# 3_waffling80-MXHS_mcu.net
KiCad netlist of a schematic drawn in Altium Designer
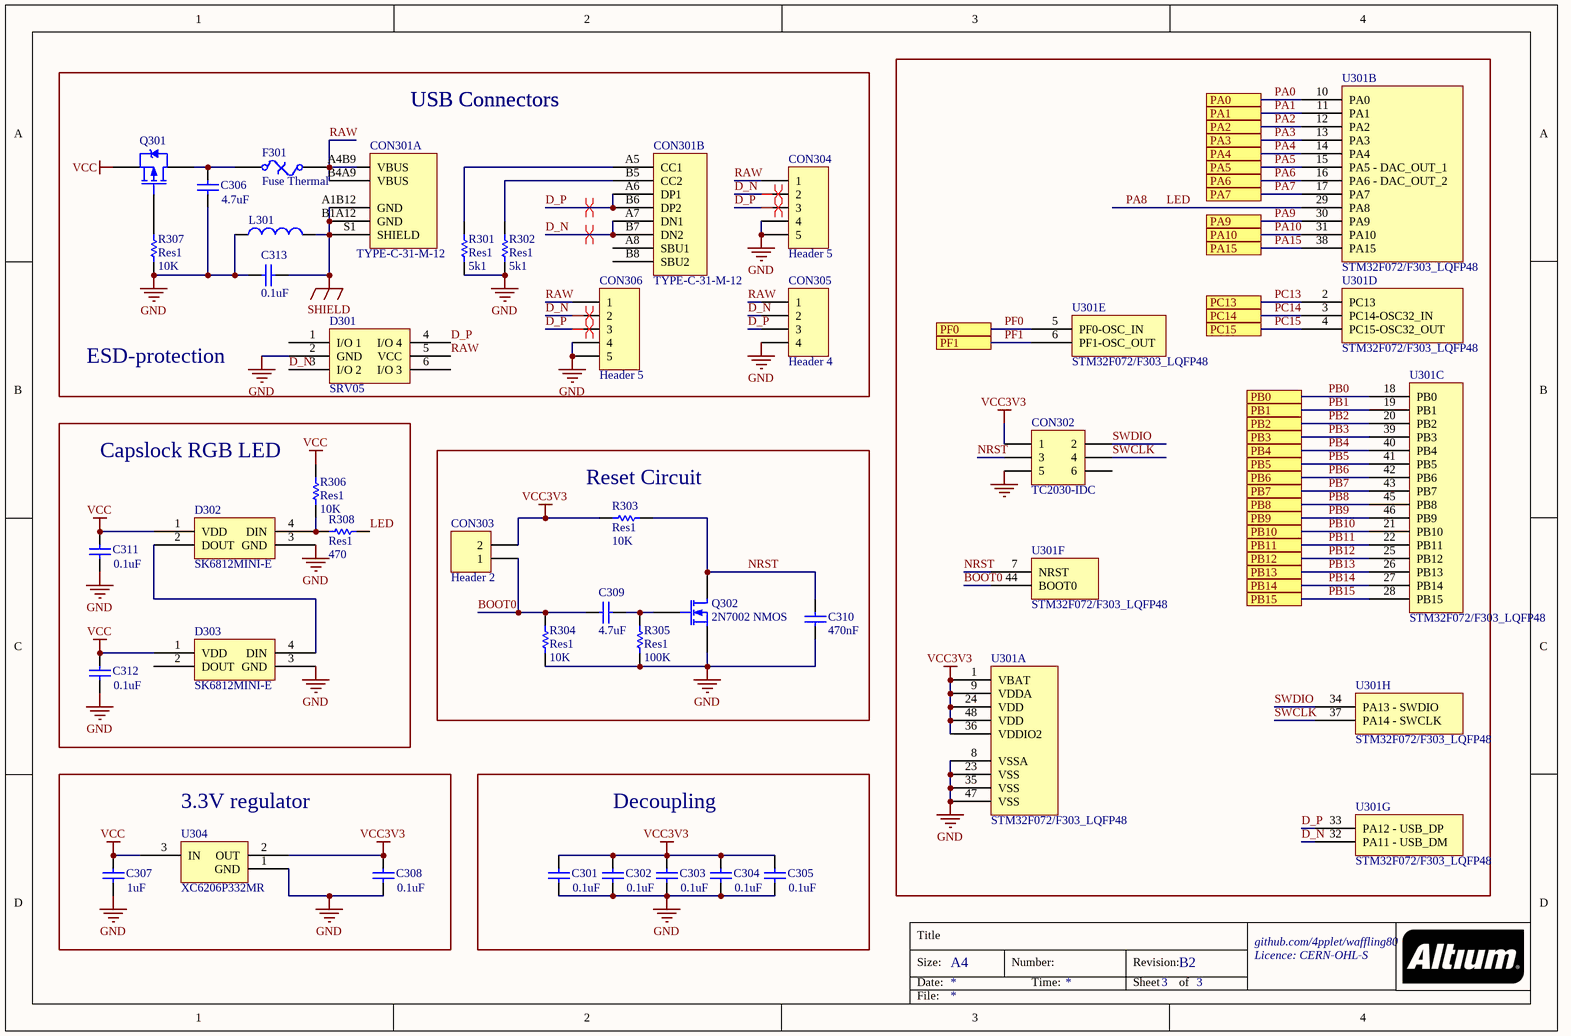
[diagram p0: 3_waffling80-MXHS_mcu.SchDoc]

(export (version "E")
  (design (tool "Eeschema 10.0.6"))
  (components
    (comp (ref "C301")
      (value "0.1uF")
      (footprint "C0603[1608]")
      (description "Capacitor")
      (fields (field (name "LCSC PART #") "C14663") (field (name "MRF.PART") "CC0603KRX7R9BB104"))
      (libsource (lib "Miscellaneous Devices") (part "Cap"))
    )
    (comp (ref "C302")
      (value "0.1uF")
      (footprint "C0603[1608]")
      (description "Capacitor")
      (fields (field (name "LCSC PART #") "C14663") (field (name "MRF.PART") "CC0603KRX7R9BB104"))
      (libsource (lib "Miscellaneous Devices") (part "Cap"))
    )
    (comp (ref "C303")
      (value "0.1uF")
      (footprint "C0603[1608]")
      (description "Capacitor")
      (fields (field (name "LCSC PART #") "C14663") (field (name "MRF.PART") "CC0603KRX7R9BB104"))
      (libsource (lib "Miscellaneous Devices") (part "Cap"))
    )
    (comp (ref "C304")
      (value "0.1uF")
      (footprint "C0603[1608]")
      (description "Capacitor")
      (fields (field (name "LCSC PART #") "C14663") (field (name "MRF.PART") "CC0603KRX7R9BB104"))
      (libsource (lib "Miscellaneous Devices") (part "Cap"))
    )
    (comp (ref "C305")
      (value "0.1uF")
      (footprint "C0603[1608]")
      (description "Capacitor")
      (fields (field (name "LCSC PART #") "C14663") (field (name "MRF.PART") "CC0603KRX7R9BB104"))
      (libsource (lib "Miscellaneous Devices") (part "Cap"))
    )
    (comp (ref "C306")
      (value "4.7uF")
      (footprint "C0603[1608]")
      (description "Capacitor")
      (fields (field (name "LCSC PART #") "C19666") (field (name "MRF.PART") "CL10A475KO8NNNC"))
      (libsource (lib "Miscellaneous Devices") (part "Cap"))
    )
    (comp (ref "C307")
      (value "1uF")
      (footprint "C0603[1608]")
      (description "Capacitor")
      (fields (field (name "LCSC PART #") "C15849") (field (name "MRF.PART") "CL10A105KB8NNNC"))
      (libsource (lib "Miscellaneous Devices") (part "Cap"))
    )
    (comp (ref "C308")
      (value "0.1uF")
      (footprint "C0603[1608]")
      (description "Capacitor")
      (fields (field (name "LCSC PART #") "C14663") (field (name "MRF.PART") "CC0603KRX7R9BB104"))
      (libsource (lib "Miscellaneous Devices") (part "Cap"))
    )
    (comp (ref "C309")
      (value "4.7uF")
      (footprint "C0603[1608]")
      (description "Capacitor")
      (fields (field (name "LCSC PART #") "C19666") (field (name "MRF.PART") "CL10A475KO8NNNC"))
      (libsource (lib "Miscellaneous Devices") (part "Cap"))
    )
    (comp (ref "C310")
      (value "470nF")
      (footprint "C0603[1608]")
      (description "Capacitor")
      (fields (field (name "LCSC PART #") "C1623") (field (name "MRF.PART") "CL10B474KA8NNNC"))
      (libsource (lib "Miscellaneous Devices") (part "Cap"))
    )
    (comp (ref "C311")
      (value "0.1uF")
      (footprint "C0603[1608]")
      (description "Capacitor")
      (fields (field (name "LCSC PART #") "C14663") (field (name "MRF.PART") "CC0603KRX7R9BB104"))
      (libsource (lib "Miscellaneous Devices") (part "Cap"))
    )
    (comp (ref "C312")
      (value "0.1uF")
      (footprint "C0603[1608]")
      (description "Capacitor")
      (fields (field (name "LCSC PART #") "C14663") (field (name "MRF.PART") "CC0603KRX7R9BB104"))
      (libsource (lib "Miscellaneous Devices") (part "Cap"))
    )
    (comp (ref "C313")
      (value "0.1uF")
      (footprint "C0603[1608]")
      (description "Capacitor")
      (fields (field (name "LCSC PART #") "C14663") (field (name "MRF.PART") "CC0603KRX7R9BB104"))
      (libsource (lib "Miscellaneous Devices") (part "Cap"))
    )
    (comp (ref "CON301")
      (value "TYPE-C-31-M-12")
      (footprint "TYPE-C-31-M-12")
      (fields (field (name "LCSC PART #") "C165948"))
      (libsource (lib "Schlib1") (part "TYPE-C-31-M-12"))
    )
    (comp (ref "CON302")
      (value "TC2030-IDC")
      (footprint "TC2030-IDC-NL")
      (description "Header, 3-Pin, Dual row")
      (libsource (lib "Miscellaneous Connectors") (part "Header 3X2"))
    )
    (comp (ref "CON303")
      (value "Header 2")
      (footprint "HDR1X2")
      (description "Header, 2-Pin")
      (libsource (lib "Miscellaneous Connectors") (part "Header 2"))
    )
    (comp (ref "CON304")
      (value "Header 5")
      (footprint "UDB_combo_JST_MOLEX")
      (description "JST for USB daughter board")
      (fields (field (name "LCSC PART #") "C160404") (field (name "MRF.PART") "SM04B-SRSS-TB(LF)(SN)"))
      (libsource (lib "Miscellaneous Connectors") (part "Header 5"))
    )
    (comp (ref "CON305")
      (value "Header 4")
      (footprint "HDR1X4")
      (description "Header, 4-Pin")
      (libsource (lib "Miscellaneous Connectors") (part "Header 4"))
    )
    (comp (ref "CON306")
      (value "Header 5")
      (footprint "Molex 781710004")
      (description "JST for USB daughter board")
      (fields (field (name "LCSC PART #") "C588524") (field (name "MRF.PART") "781710004"))
      (libsource (lib "Miscellaneous Connectors") (part "Header 5"))
    )
    (comp (ref "D301")
      (value "SRV05")
      (footprint "SOT-23-6")
      (fields (field (name "LCSC PART #") "C85364") (field (name "MRF.PART") "SRV05-4-P-T7"))
      (libsource (lib "Keebs") (part "SRV05"))
    )
    (comp (ref "D302")
      (value "SK6812MINI-E")
      (footprint "SK6812MINI-E - shaped")
      (fields (field (name "LCSC PART #") "C524051") (field (name "MRF.PART") "DY-S352818/RGBC/6812-2T"))
      (libsource (lib "Keebs") (part "SK6812MINI-E"))
    )
    (comp (ref "D303")
      (value "SK6812MINI-E")
      (footprint "SK6812MINI-E - shaped")
      (fields (field (name "LCSC PART #") "C524051") (field (name "MRF.PART") "DY-S352818/RGBC/6812-2T"))
      (libsource (lib "Keebs") (part "SK6812MINI-E"))
    )
    (comp (ref "F301")
      (value "Fuse Thermal")
      (footprint "C1206[3216]")
      (description "Thermal Fuse")
      (fields (field (name "LCSC PART #") "C135338") (field (name "MRF.PART") "ASMD1206-050"))
      (libsource (lib "Miscellaneous Devices") (part "Fuse Thermal"))
    )
    (comp (ref "L301")
      (value "Inductor")
      (footprint "L0805")
      (fields (field (name "LCSC PART #") "C1015") (field (name "MRF.PART") "GZ2012D101TF"))
      (libsource (lib "Simulation Generic Components") (part "Inductor"))
    )
    (comp (ref "Q301")
      (value "PMOS-2")
      (footprint "SOT-23-3")
      (description "P-Channel Power MOSFET")
      (fields (field (name "LCSC PART #") "C10487") (field (name "MRF.PART") "SI2301CDS-T1-GE3"))
      (libsource (lib "Miscellaneous Devices") (part "PMOS-2"))
    )
    (comp (ref "Q302")
      (value "2N7002 NMOS")
      (footprint "SOT-23-3")
      (description "N-Channel MOSFET")
      (fields (field (name "LCSC PART #") "C8545") (field (name "MRF.PART") "2N7002"))
      (libsource (lib "Miscellaneous Devices") (part "MOSFET-N"))
    )
    (comp (ref "R301")
      (value "Res1")
      (footprint "R0603[1608]")
      (description "Resistor")
      (fields
        (field (name "ALTIUM_VALUE") "5k1")
        (field (name "LCSC PART #") "C23186")
        (field (name "MRF.PART") "0603WAF5101T5E")
      )
      (libsource (lib "Miscellaneous Devices") (part "Res1"))
    )
    (comp (ref "R302")
      (value "Res1")
      (footprint "R0603[1608]")
      (description "Resistor")
      (fields
        (field (name "ALTIUM_VALUE") "5k1")
        (field (name "LCSC PART #") "C23186")
        (field (name "MRF.PART") "0603WAF5101T5E")
      )
      (libsource (lib "Miscellaneous Devices") (part "Res1"))
    )
    (comp (ref "R303")
      (value "Res1")
      (footprint "R0603[1608]")
      (description "Resistor")
      (fields
        (field (name "ALTIUM_VALUE") "10K")
        (field (name "LCSC PART #") "C25804")
        (field (name "MRF.PART") "0603WAF1002T5E")
      )
      (libsource (lib "Miscellaneous Devices") (part "Res1"))
    )
    (comp (ref "R304")
      (value "Res1")
      (footprint "R0603[1608]")
      (description "Resistor")
      (fields
        (field (name "ALTIUM_VALUE") "10K")
        (field (name "LCSC PART #") "C25804")
        (field (name "MRF.PART") "0603WAF1002T5E")
      )
      (libsource (lib "Miscellaneous Devices") (part "Res1"))
    )
    (comp (ref "R305")
      (value "Res1")
      (footprint "R0603[1608]")
      (description "Resistor")
      (fields
        (field (name "ALTIUM_VALUE") "100K")
        (field (name "LCSC PART #") "C25803")
        (field (name "MRF.PART") "0603WAF1003T5E")
      )
      (libsource (lib "Miscellaneous Devices") (part "Res1"))
    )
    (comp (ref "R306")
      (value "Res1")
      (footprint "R0603[1608]")
      (description "Resistor")
      (fields
        (field (name "ALTIUM_VALUE") "10K")
        (field (name "LCSC PART #") "C25804")
        (field (name "MRF.PART") "0603WAF1002T5E")
      )
      (libsource (lib "Miscellaneous Devices") (part "Res1"))
    )
    (comp (ref "R307")
      (value "Res1")
      (footprint "R0603[1608]")
      (description "Resistor")
      (fields
        (field (name "ALTIUM_VALUE") "10K")
        (field (name "LCSC PART #") "C25804")
        (field (name "MRF.PART") "0603WAF1002T5E")
      )
      (libsource (lib "Miscellaneous Devices") (part "Res1"))
    )
    (comp (ref "R308")
      (value "Res1")
      (footprint "R0603[1608]")
      (description "Resistor")
      (fields
        (field (name "ALTIUM_VALUE") "470")
        (field (name "LCSC PART #") "C23179")
        (field (name "MRF.PART") "0603WAF4700T5E")
      )
      (libsource (lib "Miscellaneous Devices") (part "Res1"))
    )
    (comp (ref "U301")
      (value "STM32F072/F303_LQFP48")
      (footprint "STM32 - COMBO 7X7MM")
      (fields (field (name "LCSC PART #") "C915660") (field (name "MRF.PART") "APM32F072CBT6"))
      (libsource (lib "Keebs") (part "STM32F072/F303_LQFP48"))
    )
    (comp (ref "U304")
      (value "XC6206P332MR")
      (footprint "SOT-23-3")
      (fields (field (name "LCSC PART #") "C5446"))
      (libsource (lib "Keebs") (part "SOT23 LDO"))
    )
  )
  (nets
    (net (code "1") (name "/BOOT0") (class "Default")
      (node (ref "C309") (pin "1") (pinfunction "1_1") (pintype "passive"))
      (node (ref "CON303") (pin "1") (pinfunction "1_1") (pintype "passive"))
      (node (ref "R304") (pin "1") (pinfunction "1_1") (pintype "passive"))
      (node (ref "U301") (pin "44") (pinfunction "BOOT0_44") (pintype "passive"))
    )
    (net (code "2") (name "/D_N") (class "Default")
      (node (ref "CON301") (pin "A7") (pinfunction "DN1_A7") (pintype "passive"))
      (node (ref "CON301") (pin "B7") (pinfunction "DN2_B7") (pintype "passive"))
      (node (ref "CON304") (pin "2") (pinfunction "2_2") (pintype "passive"))
      (node (ref "CON305") (pin "2") (pinfunction "2_2") (pintype "passive"))
      (node (ref "CON306") (pin "2") (pinfunction "2_2") (pintype "passive"))
      (node (ref "D301") (pin "3") (pinfunction "I/O_2_3") (pintype "passive"))
      (node (ref "U301") (pin "32") (pinfunction "PA11_-_USB_DM_32") (pintype "passive"))
    )
    (net (code "3") (name "/D_P") (class "Default")
      (node (ref "CON301") (pin "A6") (pinfunction "DP1_A6") (pintype "passive"))
      (node (ref "CON301") (pin "B6") (pinfunction "DP2_B6") (pintype "passive"))
      (node (ref "CON304") (pin "3") (pinfunction "3_3") (pintype "passive"))
      (node (ref "CON305") (pin "3") (pinfunction "3_3") (pintype "passive"))
      (node (ref "CON306") (pin "3") (pinfunction "3_3") (pintype "passive"))
      (node (ref "D301") (pin "4") (pinfunction "I/O_4_4") (pintype "passive"))
      (node (ref "U301") (pin "33") (pinfunction "PA12_-_USB_DP_33") (pintype "passive"))
    )
    (net (code "4") (name "/LED") (class "Default")
      (node (ref "R308") (pin "2") (pinfunction "2_2") (pintype "passive"))
      (node (ref "U301") (pin "29") (pinfunction "PA8_29") (pintype "passive"))
    )
    (net (code "5") (name "/NRST") (class "Default")
      (node (ref "C310") (pin "1") (pinfunction "1_1") (pintype "passive"))
      (node (ref "CON302") (pin "3") (pinfunction "3_3") (pintype "passive"))
      (node (ref "Q302") (pin "3") (pinfunction "D_3") (pintype "passive"))
      (node (ref "R303") (pin "2") (pinfunction "2_2") (pintype "passive"))
      (node (ref "U301") (pin "7") (pinfunction "NRST_7") (pintype "passive"))
    )
    (net (code "6") (name "/PA0") (class "Default")
      (node (ref "U301") (pin "10") (pinfunction "PA0_10") (pintype "passive"))
    )
    (net (code "7") (name "/PA1") (class "Default")
      (node (ref "U301") (pin "11") (pinfunction "PA1_11") (pintype "passive"))
    )
    (net (code "8") (name "/PA2") (class "Default")
      (node (ref "U301") (pin "12") (pinfunction "PA2_12") (pintype "passive"))
    )
    (net (code "9") (name "/PA3") (class "Default")
      (node (ref "U301") (pin "13") (pinfunction "PA3_13") (pintype "passive"))
    )
    (net (code "10") (name "/PA4") (class "Default")
      (node (ref "U301") (pin "14") (pinfunction "PA4_14") (pintype "passive"))
    )
    (net (code "11") (name "/PA5") (class "Default")
      (node (ref "U301") (pin "15") (pinfunction "PA5_-_DAC_OUT_1_15") (pintype "passive"))
    )
    (net (code "12") (name "/PA6") (class "Default")
      (node (ref "U301") (pin "16") (pinfunction "PA6_-_DAC_OUT_2_16") (pintype "passive"))
    )
    (net (code "13") (name "/PA7") (class "Default")
      (node (ref "U301") (pin "17") (pinfunction "PA7_17") (pintype "passive"))
    )
    (net (code "14") (name "/PA9") (class "Default")
      (node (ref "U301") (pin "30") (pinfunction "PA9_30") (pintype "passive"))
    )
    (net (code "15") (name "/PA10") (class "Default")
      (node (ref "U301") (pin "31") (pinfunction "PA10_31") (pintype "passive"))
    )
    (net (code "16") (name "/PA15") (class "Default")
      (node (ref "U301") (pin "38") (pinfunction "PA15_38") (pintype "passive"))
    )
    (net (code "17") (name "/PB0") (class "Default")
      (node (ref "U301") (pin "18") (pinfunction "PB0_18") (pintype "passive"))
    )
    (net (code "18") (name "/PB1") (class "Default")
      (node (ref "U301") (pin "19") (pinfunction "PB1_19") (pintype "passive"))
    )
    (net (code "19") (name "/PB2") (class "Default")
      (node (ref "U301") (pin "20") (pinfunction "PB2_20") (pintype "passive"))
    )
    (net (code "20") (name "/PB3") (class "Default")
      (node (ref "U301") (pin "39") (pinfunction "PB3_39") (pintype "passive"))
    )
    (net (code "21") (name "/PB4") (class "Default")
      (node (ref "U301") (pin "40") (pinfunction "PB4_40") (pintype "passive"))
    )
    (net (code "22") (name "/PB5") (class "Default")
      (node (ref "U301") (pin "41") (pinfunction "PB5_41") (pintype "passive"))
    )
    (net (code "23") (name "/PB6") (class "Default")
      (node (ref "U301") (pin "42") (pinfunction "PB6_42") (pintype "passive"))
    )
    (net (code "24") (name "/PB7") (class "Default")
      (node (ref "U301") (pin "43") (pinfunction "PB7_43") (pintype "passive"))
    )
    (net (code "25") (name "/PB8") (class "Default")
      (node (ref "U301") (pin "45") (pinfunction "PB8_45") (pintype "passive"))
    )
    (net (code "26") (name "/PB9") (class "Default")
      (node (ref "U301") (pin "46") (pinfunction "PB9_46") (pintype "passive"))
    )
    (net (code "27") (name "/PB10") (class "Default")
      (node (ref "U301") (pin "21") (pinfunction "PB10_21") (pintype "passive"))
    )
    (net (code "28") (name "/PB11") (class "Default")
      (node (ref "U301") (pin "22") (pinfunction "PB11_22") (pintype "passive"))
    )
    (net (code "29") (name "/PB12") (class "Default")
      (node (ref "U301") (pin "25") (pinfunction "PB12_25") (pintype "passive"))
    )
    (net (code "30") (name "/PB13") (class "Default")
      (node (ref "U301") (pin "26") (pinfunction "PB13_26") (pintype "passive"))
    )
    (net (code "31") (name "/PB14") (class "Default")
      (node (ref "U301") (pin "27") (pinfunction "PB14_27") (pintype "passive"))
    )
    (net (code "32") (name "/PB15") (class "Default")
      (node (ref "U301") (pin "28") (pinfunction "PB15_28") (pintype "passive"))
    )
    (net (code "33") (name "/PC13") (class "Default")
      (node (ref "U301") (pin "2") (pinfunction "PC13_2") (pintype "passive"))
    )
    (net (code "34") (name "/PC14") (class "Default")
      (node (ref "U301") (pin "3") (pinfunction "PC14-OSC32_IN_3") (pintype "passive"))
    )
    (net (code "35") (name "/PC15") (class "Default")
      (node (ref "U301") (pin "4") (pinfunction "PC15-OSC32_OUT_4") (pintype "passive"))
    )
    (net (code "36") (name "/PF0") (class "Default")
      (node (ref "U301") (pin "5") (pinfunction "PF0-OSC_IN_5") (pintype "passive"))
    )
    (net (code "37") (name "/PF1") (class "Default")
      (node (ref "U301") (pin "6") (pinfunction "PF1-OSC_OUT_6") (pintype "passive"))
    )
    (net (code "38") (name "/RAW") (class "Default")
      (node (ref "CON301") (pin "A4B9") (pinfunction "VBUS_A4B9") (pintype "passive"))
      (node (ref "CON301") (pin "B4A9") (pinfunction "VBUS_B4A9") (pintype "passive"))
      (node (ref "CON304") (pin "1") (pinfunction "1_1") (pintype "passive"))
      (node (ref "CON305") (pin "1") (pinfunction "1_1") (pintype "passive"))
      (node (ref "CON306") (pin "1") (pinfunction "1_1") (pintype "passive"))
      (node (ref "D301") (pin "5") (pinfunction "VCC_5") (pintype "passive"))
      (node (ref "F301") (pin "2") (pinfunction "2_2") (pintype "passive"))
    )
    (net (code "39") (name "/SWCLK") (class "Default")
      (node (ref "CON302") (pin "4") (pinfunction "4_4") (pintype "passive"))
      (node (ref "U301") (pin "37") (pinfunction "PA14_-_SWCLK_37") (pintype "passive"))
    )
    (net (code "40") (name "/SWDIO") (class "Default")
      (node (ref "CON302") (pin "2") (pinfunction "2_2") (pintype "passive"))
      (node (ref "U301") (pin "34") (pinfunction "PA13_-_SWDIO_34") (pintype "passive"))
    )
    (net (code "41") (name "GND") (class "Default")
      (node (ref "C301") (pin "1") (pinfunction "1_1") (pintype "passive"))
      (node (ref "C302") (pin "1") (pinfunction "1_1") (pintype "passive"))
      (node (ref "C303") (pin "1") (pinfunction "1_1") (pintype "passive"))
      (node (ref "C304") (pin "1") (pinfunction "1_1") (pintype "passive"))
      (node (ref "C305") (pin "1") (pinfunction "1_1") (pintype "passive"))
      (node (ref "C306") (pin "1") (pinfunction "1_1") (pintype "passive"))
      (node (ref "C307") (pin "1") (pinfunction "1_1") (pintype "passive"))
      (node (ref "C308") (pin "1") (pinfunction "1_1") (pintype "passive"))
      (node (ref "C310") (pin "2") (pinfunction "2_2") (pintype "passive"))
      (node (ref "C311") (pin "1") (pinfunction "1_1") (pintype "passive"))
      (node (ref "C312") (pin "1") (pinfunction "1_1") (pintype "passive"))
      (node (ref "C313") (pin "1") (pinfunction "1_1") (pintype "passive"))
      (node (ref "CON302") (pin "5") (pinfunction "5_5") (pintype "passive"))
      (node (ref "CON304") (pin "4") (pinfunction "4_4") (pintype "passive"))
      (node (ref "CON304") (pin "5") (pinfunction "5_5") (pintype "passive"))
      (node (ref "CON305") (pin "4") (pinfunction "4_4") (pintype "passive"))
      (node (ref "CON306") (pin "4") (pinfunction "4_4") (pintype "passive"))
      (node (ref "CON306") (pin "5") (pinfunction "5_5") (pintype "passive"))
      (node (ref "D301") (pin "2") (pinfunction "GND_2") (pintype "passive"))
      (node (ref "D302") (pin "3") (pinfunction "GND_3") (pintype "passive"))
      (node (ref "D303") (pin "3") (pinfunction "GND_3") (pintype "passive"))
      (node (ref "L301") (pin "1") (pinfunction "1_1") (pintype "passive"))
      (node (ref "Q302") (pin "2") (pinfunction "S_2") (pintype "passive"))
      (node (ref "R301") (pin "2") (pinfunction "2_2") (pintype "passive"))
      (node (ref "R302") (pin "2") (pinfunction "2_2") (pintype "passive"))
      (node (ref "R304") (pin "2") (pinfunction "2_2") (pintype "passive"))
      (node (ref "R305") (pin "2") (pinfunction "2_2") (pintype "passive"))
      (node (ref "R307") (pin "2") (pinfunction "2_2") (pintype "passive"))
      (node (ref "U301") (pin "23") (pinfunction "VSS_23") (pintype "passive"))
      (node (ref "U301") (pin "35") (pinfunction "VSS_35") (pintype "passive"))
      (node (ref "U301") (pin "47") (pinfunction "VSS_47") (pintype "passive"))
      (node (ref "U301") (pin "8") (pinfunction "VSSA_8") (pintype "passive"))
      (node (ref "U304") (pin "1") (pinfunction "GND_1") (pintype "passive"))
    )
    (net (code "42") (name "Net-(CON301B-CC1)") (class "Default")
      (node (ref "CON301") (pin "A5") (pinfunction "CC1_A5") (pintype "passive"))
      (node (ref "R301") (pin "1") (pinfunction "1_1") (pintype "passive"))
    )
    (net (code "43") (name "Net-(CON301B-CC2)") (class "Default")
      (node (ref "CON301") (pin "B5") (pinfunction "CC2_B5") (pintype "passive"))
      (node (ref "R302") (pin "1") (pinfunction "1_1") (pintype "passive"))
    )
    (net (code "44") (name "Net-(D302-DIN)") (class "Default")
      (node (ref "D302") (pin "4") (pinfunction "DIN_4") (pintype "passive"))
      (node (ref "R306") (pin "2") (pinfunction "2_2") (pintype "passive"))
      (node (ref "R308") (pin "1") (pinfunction "1_1") (pintype "passive"))
    )
    (net (code "45") (name "Net-(D302-DOUT)") (class "Default")
      (node (ref "D302") (pin "2") (pinfunction "DOUT_2") (pintype "passive"))
      (node (ref "D303") (pin "4") (pinfunction "DIN_4") (pintype "passive"))
    )
    (net (code "46") (name "Net-(Q301-D)") (class "Default")
      (node (ref "C306") (pin "2") (pinfunction "2_2") (pintype "passive"))
      (node (ref "F301") (pin "1") (pinfunction "1_1") (pintype "passive"))
      (node (ref "Q301") (pin "3") (pinfunction "D_3") (pintype "passive"))
    )
    (net (code "47") (name "Net-(Q301-G)") (class "Default")
      (node (ref "Q301") (pin "1") (pinfunction "G_1") (pintype "passive"))
      (node (ref "R307") (pin "1") (pinfunction "1_1") (pintype "passive"))
    )
    (net (code "48") (name "Net-(Q302-G)") (class "Default")
      (node (ref "C309") (pin "2") (pinfunction "2_2") (pintype "passive"))
      (node (ref "Q302") (pin "1") (pinfunction "G_1") (pintype "passive"))
      (node (ref "R305") (pin "1") (pinfunction "1_1") (pintype "passive"))
    )
    (net (code "49") (name "SHIELD") (class "Default")
      (node (ref "C313") (pin "2") (pinfunction "2_2") (pintype "passive"))
      (node (ref "CON301") (pin "A1B12") (pinfunction "GND_A1B12") (pintype "passive"))
      (node (ref "CON301") (pin "B1A12") (pinfunction "GND_B1A12") (pintype "passive"))
      (node (ref "CON301") (pin "S1") (pinfunction "SHIELD_S1") (pintype "passive"))
      (node (ref "L301") (pin "2") (pinfunction "2_2") (pintype "passive"))
    )
    (net (code "50") (name "VCC") (class "Default")
      (node (ref "C307") (pin "2") (pinfunction "2_2") (pintype "passive"))
      (node (ref "C311") (pin "2") (pinfunction "2_2") (pintype "passive"))
      (node (ref "C312") (pin "2") (pinfunction "2_2") (pintype "passive"))
      (node (ref "D302") (pin "1") (pinfunction "VDD_1") (pintype "passive"))
      (node (ref "D303") (pin "1") (pinfunction "VDD_1") (pintype "passive"))
      (node (ref "Q301") (pin "2") (pinfunction "S_2") (pintype "passive"))
      (node (ref "R306") (pin "1") (pinfunction "1_1") (pintype "passive"))
      (node (ref "U304") (pin "3") (pinfunction "IN_3") (pintype "passive"))
    )
    (net (code "51") (name "VCC3V3") (class "Default")
      (node (ref "C301") (pin "2") (pinfunction "2_2") (pintype "passive"))
      (node (ref "C302") (pin "2") (pinfunction "2_2") (pintype "passive"))
      (node (ref "C303") (pin "2") (pinfunction "2_2") (pintype "passive"))
      (node (ref "C304") (pin "2") (pinfunction "2_2") (pintype "passive"))
      (node (ref "C305") (pin "2") (pinfunction "2_2") (pintype "passive"))
      (node (ref "C308") (pin "2") (pinfunction "2_2") (pintype "passive"))
      (node (ref "CON302") (pin "1") (pinfunction "1_1") (pintype "passive"))
      (node (ref "CON303") (pin "2") (pinfunction "2_2") (pintype "passive"))
      (node (ref "R303") (pin "1") (pinfunction "1_1") (pintype "passive"))
      (node (ref "U301") (pin "1") (pinfunction "VBAT_1") (pintype "passive"))
      (node (ref "U301") (pin "24") (pinfunction "VDD_24") (pintype "passive"))
      (node (ref "U301") (pin "36") (pinfunction "VDDIO2_36") (pintype "passive"))
      (node (ref "U301") (pin "48") (pinfunction "VDD_48") (pintype "passive"))
      (node (ref "U301") (pin "9") (pinfunction "VDDA_9") (pintype "passive"))
      (node (ref "U304") (pin "2") (pinfunction "OUT_2") (pintype "passive"))
    )
    (net (code "52") (name "unconnected-(CON301B-SBU1-PadA8)") (class "Default")
      (node (ref "CON301") (pin "A8") (pinfunction "SBU1_A8") (pintype "passive"))
    )
    (net (code "53") (name "unconnected-(CON301B-SBU2-PadB8)") (class "Default")
      (node (ref "CON301") (pin "B8") (pinfunction "SBU2_B8") (pintype "passive"))
    )
    (net (code "54") (name "unconnected-(CON302-Pad6)") (class "Default")
      (node (ref "CON302") (pin "6") (pinfunction "6_6") (pintype "passive"))
    )
    (net (code "55") (name "unconnected-(D301-I{slash}O_1-Pad1)") (class "Default")
      (node (ref "D301") (pin "1") (pinfunction "I/O_1_1") (pintype "passive"))
    )
    (net (code "56") (name "unconnected-(D301-I{slash}O_3-Pad6)") (class "Default")
      (node (ref "D301") (pin "6") (pinfunction "I/O_3_6") (pintype "passive"))
    )
    (net (code "57") (name "unconnected-(D303-DOUT-Pad2)") (class "Default")
      (node (ref "D303") (pin "2") (pinfunction "DOUT_2") (pintype "passive"))
    )
  )
)
